# SCH_RailRoadLights_2025-12-05.net
KiCad netlist of a schematic drawn in EasyEDA
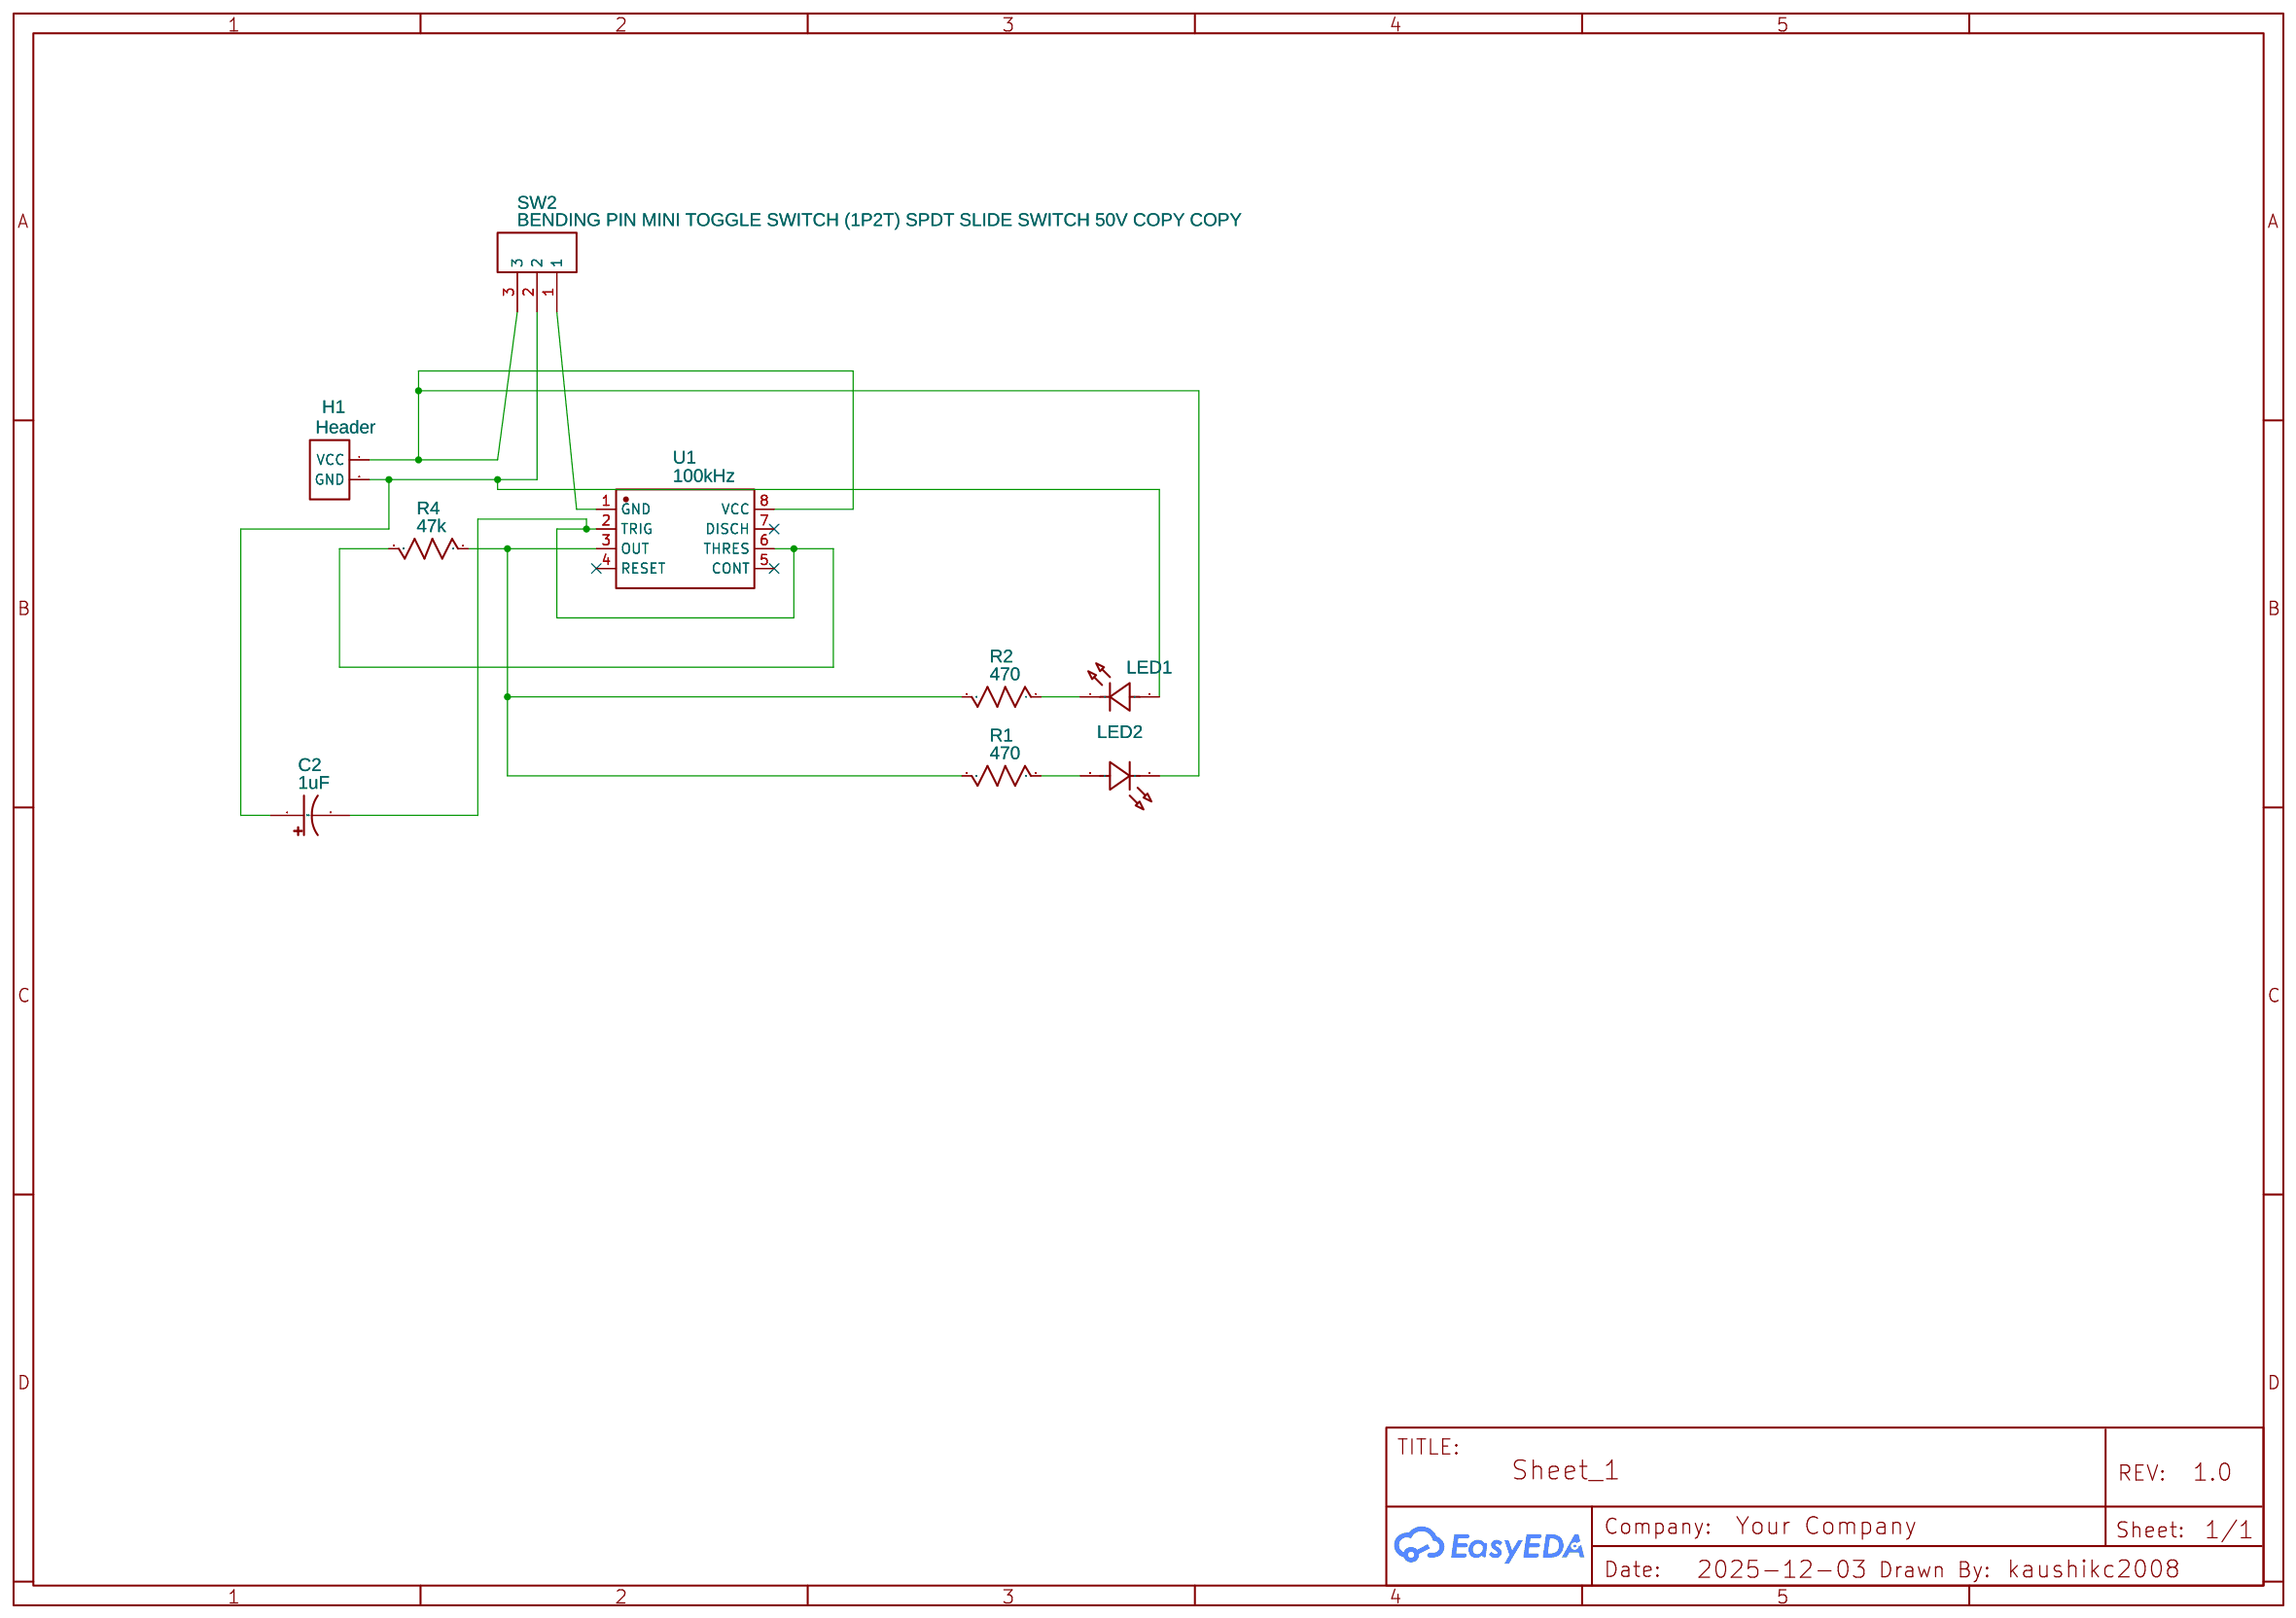
[diagram p0: schematic sheet]

(export (version "E")
  (design (tool "Eeschema 10.0.6"))
  (components
    (comp (ref "C2")
      (value "1uF")
      (fields (field (name "Manufacturer Part") "UVZ1H010MDD") (field (name "Manufacturer") "Nichicon(尼吉康)"))
      (libsource (lib "") (part "UVZ1H010MDD"))
    )
    (comp (ref "H1") (value "Header") (libsource (lib "") (part "HEADER-FEMALE-2.54_1X2")))
    (comp (ref "LED1")
      (value "XL-502UWC")
      (fields (field (name "Manufacturer") "XINGLIGHT(成兴光)"))
      (libsource (lib "") (part "XL-502UWC"))
    )
    (comp (ref "LED2")
      (value "XL-502UWC")
      (fields (field (name "Manufacturer") "XINGLIGHT(成兴光)"))
      (libsource (lib "") (part "XL-502UWC_1"))
    )
    (comp (ref "R1")
      (value "470")
      (fields
        (field (name "Manufacturer Part") "MF1/4W-1KΩ±1%T52")
        (field (name "Manufacturer") "Huaxing Mechanical-Elec.")
      )
      (libsource (lib "") (part "R_0603_US"))
    )
    (comp (ref "R2")
      (value "470")
      (fields
        (field (name "Manufacturer Part") "MF1/4W-1KΩ±1%T52")
        (field (name "Manufacturer") "Huaxing Mechanical-Elec.")
      )
      (libsource (lib "") (part "R_0603_US"))
    )
    (comp (ref "R4")
      (value "47k")
      (fields
        (field (name "Manufacturer Part") "MF1/4W-1KΩ±1%T52")
        (field (name "Manufacturer") "Huaxing Mechanical-Elec.")
      )
      (libsource (lib "") (part "R_0603_US"))
    )
    (comp (ref "SW2")
      (value "BENDING PIN MINI TOGGLE SWITCH (1P2T) SPDT SLIDE SWITCH 50V COPY COPY")
      (fields
        (field (name "Manufacturer Part") "SS12D06")
        (field (name "Manufacturer") "Dongguan Kaifeng Electronic Technology Limited")
      )
      (libsource (lib "") (part "BENDING PIN MINI TOGGLE SWITCH (1P2T) SPDT SLIDE SWITCH 50V COPY COPY"))
    )
    (comp (ref "U1")
      (value "100kHz")
      (fields (field (name "Manufacturer Part") "NE555P") (field (name "Manufacturer") "TI(德州仪器)"))
      (libsource (lib "") (part "NE555P"))
    )
  )
  (nets
    (net (code "1") (name "Net-(H1-GND)") (class "Default")
      (node (ref "C2") (pin "1") (pinfunction "1_1") (pintype "unspecified"))
      (node (ref "H1") (pin "2") (pinfunction "GND_2") (pintype "unspecified"))
      (node (ref "LED1") (pin "2") (pinfunction "A_2") (pintype "unspecified"))
      (node (ref "SW2") (pin "2") (pinfunction "2_2") (pintype "unspecified"))
    )
    (net (code "2") (name "Net-(H1-VCC)") (class "Default")
      (node (ref "H1") (pin "1") (pinfunction "VCC_1") (pintype "unspecified"))
      (node (ref "LED2") (pin "1") (pinfunction "K_1") (pintype "unspecified"))
      (node (ref "SW2") (pin "3") (pinfunction "3_3") (pintype "unspecified"))
      (node (ref "U1") (pin "8") (pinfunction "VCC_8") (pintype "unspecified"))
    )
    (net (code "3") (name "Net-(LED1-K)") (class "Default")
      (node (ref "LED1") (pin "1") (pinfunction "K_1") (pintype "unspecified"))
      (node (ref "R2") (pin "1") (pinfunction "1_1") (pintype "unspecified"))
    )
    (net (code "4") (name "Net-(LED2-A)") (class "Default")
      (node (ref "LED2") (pin "2") (pinfunction "A_2") (pintype "unspecified"))
      (node (ref "R1") (pin "1") (pinfunction "1_1") (pintype "unspecified"))
    )
    (net (code "5") (name "Net-(U1-GND)") (class "Default")
      (node (ref "SW2") (pin "1") (pinfunction "1_1") (pintype "unspecified"))
      (node (ref "U1") (pin "1") (pinfunction "GND_1") (pintype "unspecified"))
    )
    (net (code "6") (name "Net-(U1-OUT)") (class "Default")
      (node (ref "R1") (pin "2") (pinfunction "2_2") (pintype "unspecified"))
      (node (ref "R2") (pin "2") (pinfunction "2_2") (pintype "unspecified"))
      (node (ref "R4") (pin "1") (pinfunction "1_1") (pintype "unspecified"))
      (node (ref "U1") (pin "3") (pinfunction "OUT_3") (pintype "unspecified"))
    )
    (net (code "7") (name "Net-(U1-THRES)") (class "Default")
      (node (ref "C2") (pin "2") (pinfunction "2_2") (pintype "unspecified"))
      (node (ref "R4") (pin "2") (pinfunction "2_2") (pintype "unspecified"))
      (node (ref "U1") (pin "2") (pinfunction "TRIG_2") (pintype "unspecified"))
      (node (ref "U1") (pin "6") (pinfunction "THRES_6") (pintype "unspecified"))
    )
    (net (code "8") (name "unconnected-(U1-CONT-Pad5)") (class "Default")
      (node (ref "U1") (pin "5") (pinfunction "CONT_5") (pintype "unspecified+no_connect"))
    )
    (net (code "9") (name "unconnected-(U1-DISCH-Pad7)") (class "Default")
      (node (ref "U1") (pin "7") (pinfunction "DISCH_7") (pintype "unspecified+no_connect"))
    )
    (net (code "10") (name "unconnected-(U1-RESET-Pad4)") (class "Default")
      (node (ref "U1") (pin "4") (pinfunction "RESET_4") (pintype "unspecified+no_connect"))
    )
  )
)
